# shield-ble.net
KiCad netlist of a schematic drawn in EAGLE
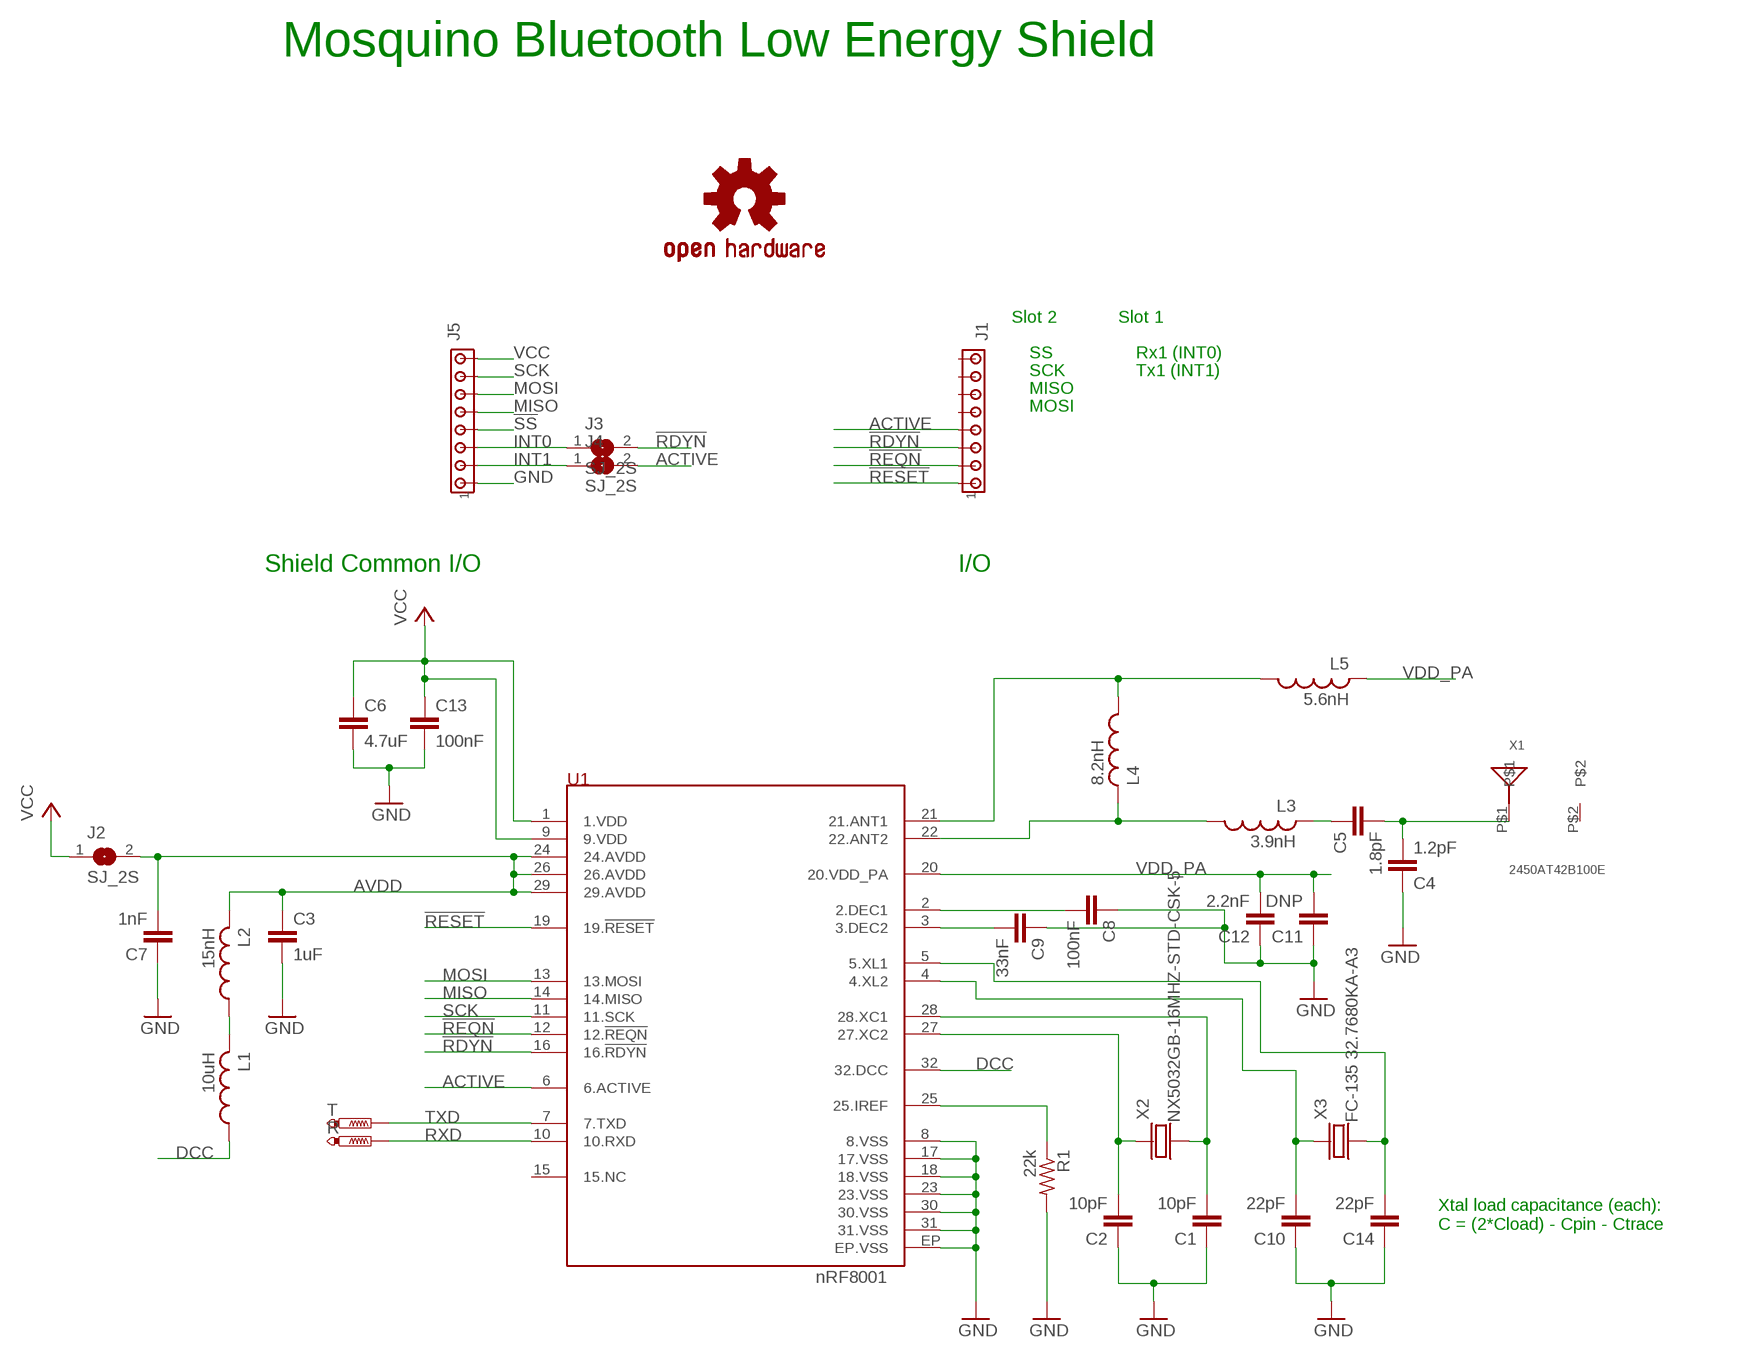
[diagram p0: schematic, sheet 1]

(export (version "E")
  (design (tool "Eeschema 10.0.6"))
  (components
    (comp (ref "C1")
      (value "10pF")
      (footprint "eagle-import:C0603")
      (libsource (lib "eagle-import") (part "C-EUC0603"))
    )
    (comp (ref "C2")
      (value "10pF")
      (footprint "eagle-import:C0603")
      (libsource (lib "eagle-import") (part "C-EUC0603"))
    )
    (comp (ref "C3")
      (value "1uF")
      (footprint "eagle-import:C0603")
      (libsource (lib "eagle-import") (part "C-EUC0603"))
    )
    (comp (ref "C4")
      (value "1.2pF")
      (footprint "eagle-import:C0603")
      (libsource (lib "eagle-import") (part "C-EUC0603"))
    )
    (comp (ref "C5")
      (value "1.8pF")
      (footprint "eagle-import:C0603")
      (libsource (lib "eagle-import") (part "C-EUC0603"))
    )
    (comp (ref "C6")
      (value "4.7uF")
      (footprint "eagle-import:C0603")
      (libsource (lib "eagle-import") (part "C-EUC0603"))
    )
    (comp (ref "C7")
      (value "1nF")
      (footprint "eagle-import:C0603")
      (libsource (lib "eagle-import") (part "C-EUC0603"))
    )
    (comp (ref "C8")
      (value "100nF")
      (footprint "eagle-import:C0603")
      (libsource (lib "eagle-import") (part "C-EUC0603"))
    )
    (comp (ref "C9")
      (value "33nF")
      (footprint "eagle-import:C0603")
      (libsource (lib "eagle-import") (part "C-EUC0603"))
    )
    (comp (ref "C10")
      (value "22pF")
      (footprint "eagle-import:C0603")
      (libsource (lib "eagle-import") (part "C-EUC0603"))
    )
    (comp (ref "C11")
      (value "DNP")
      (footprint "eagle-import:C0603")
      (libsource (lib "eagle-import") (part "C-EUC0603"))
    )
    (comp (ref "C12")
      (value "2.2nF")
      (footprint "eagle-import:C0603")
      (libsource (lib "eagle-import") (part "C-EUC0603"))
    )
    (comp (ref "C13")
      (value "100nF")
      (footprint "eagle-import:C0603")
      (libsource (lib "eagle-import") (part "C-EUC0603"))
    )
    (comp (ref "C14")
      (value "22pF")
      (footprint "eagle-import:C0603")
      (libsource (lib "eagle-import") (part "C-EUC0603"))
    )
    (comp (ref "J1")
      (value "MTA08-100")
      (footprint "eagle-import:10X08MTA")
      (libsource (lib "eagle-import") (part "MTA08-100"))
    )
    (comp (ref "J2")
      (value "SJ_2S")
      (footprint "eagle-import:SJ2_S")
      (libsource (lib "eagle-import") (part "SJ_2S"))
    )
    (comp (ref "J3")
      (value "SJ_2S")
      (footprint "eagle-import:SJ2_S")
      (libsource (lib "eagle-import") (part "SJ_2S"))
    )
    (comp (ref "J4")
      (value "SJ_2S")
      (footprint "eagle-import:SJ2_S")
      (libsource (lib "eagle-import") (part "SJ_2S"))
    )
    (comp (ref "J5")
      (value "MTA08-100")
      (footprint "eagle-import:10X08MTA")
      (libsource (lib "eagle-import") (part "MTA08-100"))
    )
    (comp (ref "L1")
      (value "10uH")
      (footprint "eagle-import:0603")
      (libsource (lib "eagle-import") (part "L-GENERIC0603"))
    )
    (comp (ref "L2")
      (value "15nH")
      (footprint "eagle-import:0603")
      (libsource (lib "eagle-import") (part "L-GENERIC0603"))
    )
    (comp (ref "L3")
      (value "3.9nH")
      (footprint "eagle-import:0603")
      (libsource (lib "eagle-import") (part "L-GENERIC0603"))
    )
    (comp (ref "L4")
      (value "8.2nH")
      (footprint "eagle-import:0603")
      (libsource (lib "eagle-import") (part "L-GENERIC0603"))
    )
    (comp (ref "L5")
      (value "5.6nH")
      (footprint "eagle-import:0603")
      (libsource (lib "eagle-import") (part "L-GENERIC0603"))
    )
    (comp (ref "LOGO1")
      (value "OSHW-LOGOS")
      (footprint "eagle-import:OSHW-LOGO-S")
      (libsource (lib "eagle-import") (part "OSHW-LOGOS"))
    )
    (comp (ref "R")
      (value "PTR1PAD1-13")
      (footprint "eagle-import:P1-13")
      (libsource (lib "eagle-import") (part "PTR1PAD1-13"))
    )
    (comp (ref "R1")
      (value "22k")
      (footprint "eagle-import:R0603")
      (libsource (lib "eagle-import") (part "R-US_R0603"))
    )
    (comp (ref "T")
      (value "PTR1PAD1-13")
      (footprint "eagle-import:P1-13")
      (libsource (lib "eagle-import") (part "PTR1PAD1-13"))
    )
    (comp (ref "U1")
      (value "NRF8001_QFN32")
      (footprint "eagle-import:QFN-32")
      (libsource (lib "eagle-import") (part "NRF8001_QFN32"))
    )
    (comp (ref "X1")
      (value "2450AT42B100E")
      (footprint "eagle-import:ANTENNA_CHIP_5MMX2MM")
      (libsource (lib "eagle-import") (part "ANTENNA_CHIP_5MMX2MM"))
    )
    (comp (ref "X2")
      (value "NX5032GB-16MHZ-STD-CSK-5")
      (footprint "eagle-import:CRYSTAL_SMD_5X3POINT2MM")
      (libsource (lib "eagle-import") (part "CRYSTAL_SMD_5X3POINT2MM"))
    )
    (comp (ref "X3")
      (value "FC-135 32.7680KA-A3")
      (footprint "eagle-import:FC-135")
      (libsource (lib "eagle-import") (part "FC-135"))
    )
  )
  (nets
    (net (code "1") (name "/ACTIVE") (class "Default")
      (node (ref "J1") (pin "4") (pinfunction "4_4") (pintype "passive"))
      (node (ref "J4") (pin "2") (pinfunction "2_2") (pintype "passive"))
      (node (ref "U1") (pin "6") (pinfunction "6.ACTIVE_6") (pintype "bidirectional"))
    )
    (net (code "2") (name "/AVDD") (class "Default")
      (node (ref "C3") (pin "1") (pinfunction "1_1") (pintype "passive"))
      (node (ref "C7") (pin "2") (pinfunction "2_2") (pintype "passive"))
      (node (ref "J2") (pin "2") (pinfunction "2_2") (pintype "passive"))
      (node (ref "L2") (pin "2") (pinfunction "2_2") (pintype "passive"))
      (node (ref "U1") (pin "24") (pinfunction "24.AVDD_24") (pintype "power_in"))
      (node (ref "U1") (pin "26") (pinfunction "26.AVDD_26") (pintype "power_in"))
      (node (ref "U1") (pin "29") (pinfunction "29.AVDD_29") (pintype "power_in"))
    )
    (net (code "3") (name "/DCC") (class "Default")
      (node (ref "L1") (pin "1") (pinfunction "1_1") (pintype "passive"))
      (node (ref "U1") (pin "32") (pinfunction "32.DCC_32") (pintype "bidirectional"))
    )
    (net (code "4") (name "/INT0") (class "Default")
      (node (ref "J3") (pin "1") (pinfunction "1_1") (pintype "passive"))
      (node (ref "J5") (pin "3") (pinfunction "3_3") (pintype "passive"))
    )
    (net (code "5") (name "/INT1") (class "Default")
      (node (ref "J4") (pin "1") (pinfunction "1_1") (pintype "passive"))
      (node (ref "J5") (pin "2") (pinfunction "2_2") (pintype "passive"))
    )
    (net (code "6") (name "/MISO") (class "Default")
      (node (ref "J5") (pin "5") (pinfunction "5_5") (pintype "passive"))
      (node (ref "U1") (pin "14") (pinfunction "14.MISO_14") (pintype "bidirectional"))
    )
    (net (code "7") (name "/MOSI") (class "Default")
      (node (ref "J5") (pin "6") (pinfunction "6_6") (pintype "passive"))
      (node (ref "U1") (pin "13") (pinfunction "13.MOSI_13") (pintype "bidirectional"))
    )
    (net (code "8") (name "/RXD") (class "Default")
      (node (ref "R") (pin "TP") (pinfunction "TP_TP") (pintype "input"))
      (node (ref "U1") (pin "10") (pinfunction "10.RXD_10") (pintype "bidirectional"))
    )
    (net (code "9") (name "/SCK") (class "Default")
      (node (ref "J5") (pin "7") (pinfunction "7_7") (pintype "passive"))
      (node (ref "U1") (pin "11") (pinfunction "11.SCK_11") (pintype "bidirectional"))
    )
    (net (code "10") (name "/TXD") (class "Default")
      (node (ref "T") (pin "TP") (pinfunction "TP_TP") (pintype "input"))
      (node (ref "U1") (pin "7") (pinfunction "7.TXD_7") (pintype "bidirectional"))
    )
    (net (code "11") (name "/VDD_PA") (class "Default")
      (node (ref "C11") (pin "2") (pinfunction "2_2") (pintype "passive"))
      (node (ref "C12") (pin "2") (pinfunction "2_2") (pintype "passive"))
      (node (ref "L5") (pin "2") (pinfunction "2_2") (pintype "passive"))
      (node (ref "U1") (pin "20") (pinfunction "20.VDD_PA_20") (pintype "bidirectional"))
    )
    (net (code "12") (name "/~{RDYN}") (class "Default")
      (node (ref "J1") (pin "3") (pinfunction "3_3") (pintype "passive"))
      (node (ref "J3") (pin "2") (pinfunction "2_2") (pintype "passive"))
      (node (ref "U1") (pin "16") (pinfunction "16.~{RDYN}_16") (pintype "bidirectional"))
    )
    (net (code "13") (name "/~{REQN}") (class "Default")
      (node (ref "J1") (pin "2") (pinfunction "2_2") (pintype "passive"))
      (node (ref "U1") (pin "12") (pinfunction "12.~{REQN}_12") (pintype "bidirectional"))
    )
    (net (code "14") (name "/~{RESET}") (class "Default")
      (node (ref "J1") (pin "1") (pinfunction "1_1") (pintype "passive"))
      (node (ref "U1") (pin "19") (pinfunction "19.~{RESET}_19") (pintype "bidirectional"))
    )
    (net (code "15") (name "/~{SS}") (class "Default")
      (node (ref "J5") (pin "4") (pinfunction "4_4") (pintype "passive"))
    )
    (net (code "16") (name "GND") (class "Default")
      (node (ref "C1") (pin "1") (pinfunction "1_1") (pintype "passive"))
      (node (ref "C10") (pin "1") (pinfunction "1_1") (pintype "passive"))
      (node (ref "C11") (pin "1") (pinfunction "1_1") (pintype "passive"))
      (node (ref "C12") (pin "1") (pinfunction "1_1") (pintype "passive"))
      (node (ref "C13") (pin "2") (pinfunction "2_2") (pintype "passive"))
      (node (ref "C14") (pin "1") (pinfunction "1_1") (pintype "passive"))
      (node (ref "C2") (pin "1") (pinfunction "1_1") (pintype "passive"))
      (node (ref "C3") (pin "2") (pinfunction "2_2") (pintype "passive"))
      (node (ref "C4") (pin "1") (pinfunction "1_1") (pintype "passive"))
      (node (ref "C6") (pin "2") (pinfunction "2_2") (pintype "passive"))
      (node (ref "C7") (pin "1") (pinfunction "1_1") (pintype "passive"))
      (node (ref "C8") (pin "1") (pinfunction "1_1") (pintype "passive"))
      (node (ref "C9") (pin "1") (pinfunction "1_1") (pintype "passive"))
      (node (ref "J5") (pin "1") (pinfunction "1_1") (pintype "passive"))
      (node (ref "R1") (pin "2") (pinfunction "2_2") (pintype "passive"))
      (node (ref "U1") (pin "17") (pinfunction "17.VSS_17") (pintype "power_in"))
      (node (ref "U1") (pin "18") (pinfunction "18.VSS_18") (pintype "power_in"))
      (node (ref "U1") (pin "23") (pinfunction "23.VSS_23") (pintype "power_in"))
      (node (ref "U1") (pin "30") (pinfunction "30.VSS_30") (pintype "power_in"))
      (node (ref "U1") (pin "31") (pinfunction "31.VSS_31") (pintype "power_in"))
      (node (ref "U1") (pin "8") (pinfunction "8.VSS_8") (pintype "power_in"))
      (node (ref "U1") (pin "EP") (pinfunction "EP.VSS_EP") (pintype "power_in"))
    )
    (net (code "17") (name "Net-(C4-Pad2)") (class "Default")
      (node (ref "C4") (pin "2") (pinfunction "2_2") (pintype "passive"))
      (node (ref "C5") (pin "2") (pinfunction "2_2") (pintype "passive"))
      (node (ref "X1") (pin "P$1") (pinfunction "P$1_P$1") (pintype "passive"))
    )
    (net (code "18") (name "Net-(C5-Pad1)") (class "Default")
      (node (ref "C5") (pin "1") (pinfunction "1_1") (pintype "passive"))
      (node (ref "L3") (pin "2") (pinfunction "2_2") (pintype "passive"))
    )
    (net (code "19") (name "Net-(L1-Pad2)") (class "Default")
      (node (ref "L1") (pin "2") (pinfunction "2_2") (pintype "passive"))
      (node (ref "L2") (pin "1") (pinfunction "1_1") (pintype "passive"))
    )
    (net (code "20") (name "Net-(U1-2.DEC1)") (class "Default")
      (node (ref "C8") (pin "2") (pinfunction "2_2") (pintype "passive"))
      (node (ref "U1") (pin "2") (pinfunction "2.DEC1_2") (pintype "bidirectional"))
    )
    (net (code "21") (name "Net-(U1-3.DEC2)") (class "Default")
      (node (ref "C9") (pin "2") (pinfunction "2_2") (pintype "passive"))
      (node (ref "U1") (pin "3") (pinfunction "3.DEC2_3") (pintype "bidirectional"))
    )
    (net (code "22") (name "Net-(U1-4.XL2)") (class "Default")
      (node (ref "C10") (pin "2") (pinfunction "2_2") (pintype "passive"))
      (node (ref "U1") (pin "4") (pinfunction "4.XL2_4") (pintype "bidirectional"))
      (node (ref "X3") (pin "P$1") (pinfunction "X1_P$1") (pintype "passive"))
    )
    (net (code "23") (name "Net-(U1-5.XL1)") (class "Default")
      (node (ref "C14") (pin "2") (pinfunction "2_2") (pintype "passive"))
      (node (ref "U1") (pin "5") (pinfunction "5.XL1_5") (pintype "bidirectional"))
      (node (ref "X3") (pin "P$2") (pinfunction "X2_P$2") (pintype "passive"))
    )
    (net (code "24") (name "Net-(U1-21.ANT1)") (class "Default")
      (node (ref "L4") (pin "1") (pinfunction "1_1") (pintype "passive"))
      (node (ref "L5") (pin "1") (pinfunction "1_1") (pintype "passive"))
      (node (ref "U1") (pin "21") (pinfunction "21.ANT1_21") (pintype "output"))
    )
    (net (code "25") (name "Net-(U1-22.ANT2)") (class "Default")
      (node (ref "L3") (pin "1") (pinfunction "1_1") (pintype "passive"))
      (node (ref "L4") (pin "2") (pinfunction "2_2") (pintype "passive"))
      (node (ref "U1") (pin "22") (pinfunction "22.ANT2_22") (pintype "output"))
    )
    (net (code "26") (name "Net-(U1-25.IREF)") (class "Default")
      (node (ref "R1") (pin "1") (pinfunction "1_1") (pintype "passive"))
      (node (ref "U1") (pin "25") (pinfunction "25.IREF_25") (pintype "bidirectional"))
    )
    (net (code "27") (name "Net-(U1-27.XC2)") (class "Default")
      (node (ref "C2") (pin "2") (pinfunction "2_2") (pintype "passive"))
      (node (ref "U1") (pin "27") (pinfunction "27.XC2_27") (pintype "bidirectional"))
      (node (ref "X2") (pin "P$1") (pinfunction "X1_P$1") (pintype "passive"))
    )
    (net (code "28") (name "Net-(U1-28.XC1)") (class "Default")
      (node (ref "C1") (pin "2") (pinfunction "2_2") (pintype "passive"))
      (node (ref "U1") (pin "28") (pinfunction "28.XC1_28") (pintype "bidirectional"))
      (node (ref "X2") (pin "P$2") (pinfunction "X2_P$2") (pintype "passive"))
    )
    (net (code "29") (name "VCC") (class "Default")
      (node (ref "C13") (pin "1") (pinfunction "1_1") (pintype "passive"))
      (node (ref "C6") (pin "1") (pinfunction "1_1") (pintype "passive"))
      (node (ref "J2") (pin "1") (pinfunction "1_1") (pintype "passive"))
      (node (ref "J5") (pin "8") (pinfunction "8_8") (pintype "passive"))
      (node (ref "U1") (pin "1") (pinfunction "1.VDD_1") (pintype "power_in"))
      (node (ref "U1") (pin "9") (pinfunction "9.VDD_9") (pintype "power_in"))
    )
    (net (code "30") (name "unconnected-(J1-Pad5)") (class "Default")
      (node (ref "J1") (pin "5") (pinfunction "5_5") (pintype "passive"))
    )
    (net (code "31") (name "unconnected-(J1-Pad6)") (class "Default")
      (node (ref "J1") (pin "6") (pinfunction "6_6") (pintype "passive"))
    )
    (net (code "32") (name "unconnected-(J1-Pad7)") (class "Default")
      (node (ref "J1") (pin "7") (pinfunction "7_7") (pintype "passive"))
    )
    (net (code "33") (name "unconnected-(J1-Pad8)") (class "Default")
      (node (ref "J1") (pin "8") (pinfunction "8_8") (pintype "passive"))
    )
    (net (code "34") (name "unconnected-(U1-15.NC-Pad15)") (class "Default")
      (node (ref "U1") (pin "15") (pinfunction "15.NC_15") (pintype "bidirectional"))
    )
    (net (code "35") (name "unconnected-(X1-PadP$2)") (class "Default")
      (node (ref "X1") (pin "P$2") (pinfunction "P$2_P$2") (pintype "passive"))
    )
  )
)
